# PWR_FG.net
KiCad netlist of a schematic drawn in Altium Designer
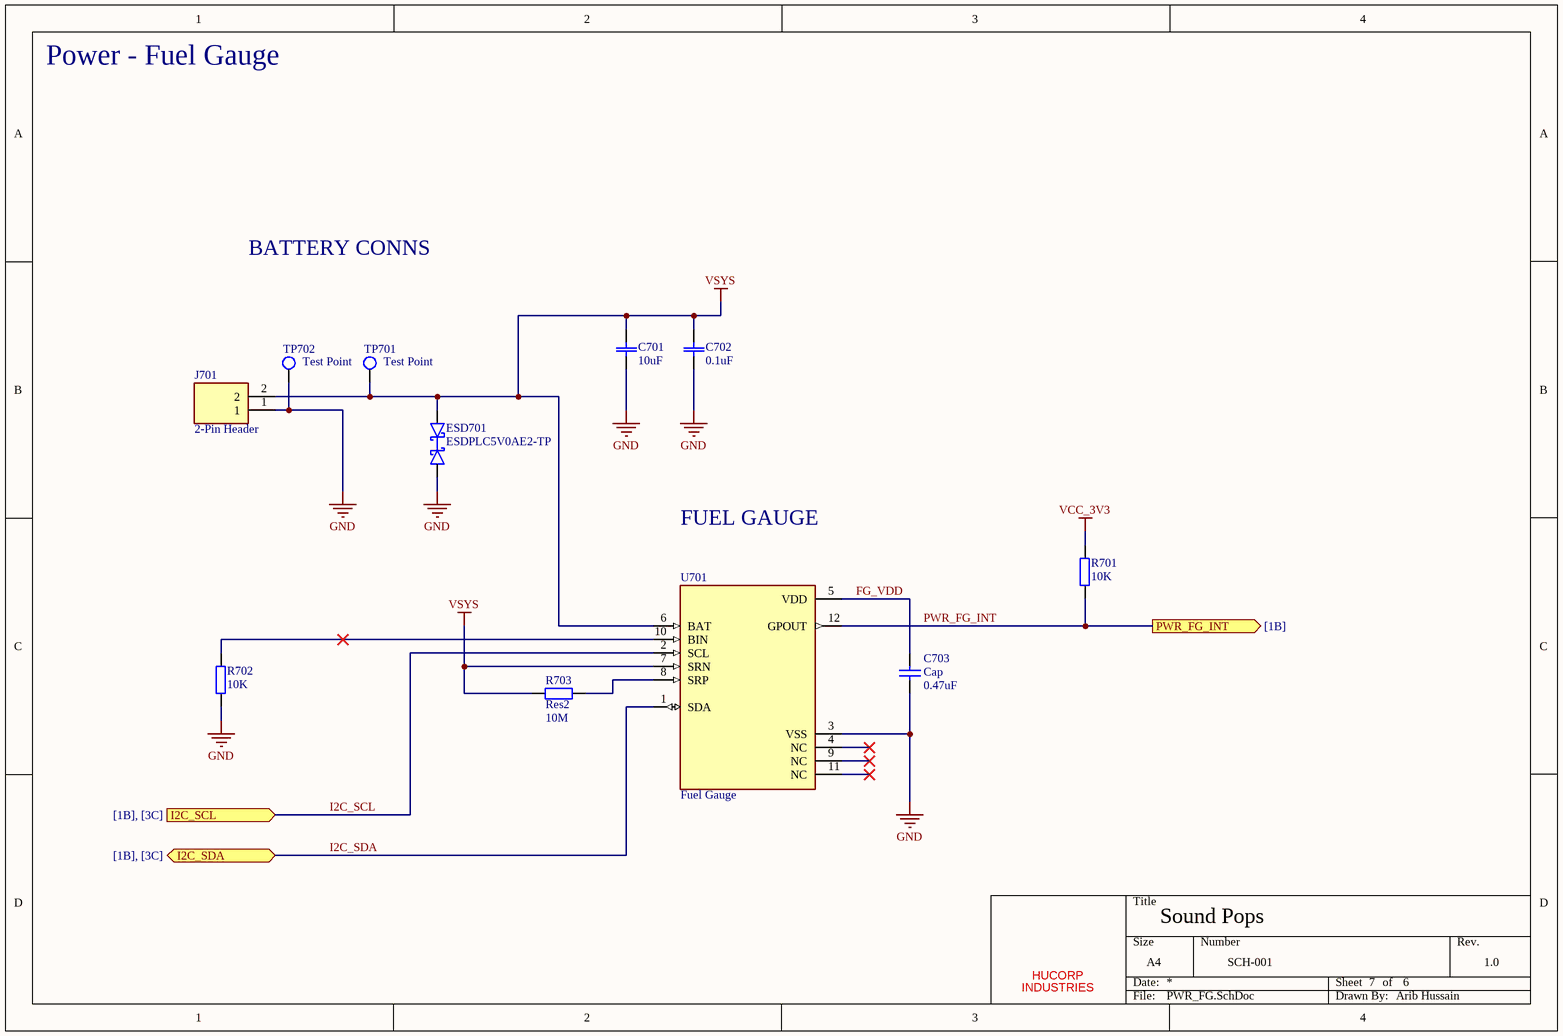
[diagram p0: PWR_FG.SchDoc]

(export (version "E")
  (design (tool "Eeschema 10.0.6"))
  (components
    (comp (ref "C701")
      (value "10uF")
      (footprint "CAP_CL10_SAM")
      (description "10 µF ±20% 6.3V Ceramic Capacitor X5R 0603 (1608 Metric)")
      (fields
        (field (name "MANUFACTURER_PART_NUMBER") "CL10A106MQ8NNNC")
        (field (name "Comment") "10 uF")
        (field (name "COPYRIGHT") "Copyright (C) 2022 Ultra Librarian. All rights reserved.")
      )
      (libsource (lib "Capacitors") (part "CL10A106MQ8NNNC"))
    )
    (comp (ref "C702")
      (value "0.1uF")
      (footprint "CAP_CL10_SAM")
      (description "CAP CER 0.1UF 25V X7R 0603")
      (fields
        (field (name "MANUFACTURER_PART_NUMBER") "CL10B104KA8NNNC")
        (field (name "Comment") "100 nF")
        (field (name "COPYRIGHT") "Copyright (C) 2022 Ultra Librarian. All rights reserved.")
      )
      (libsource (lib "Capacitors") (part "CL10B104KA8NNNC"))
    )
    (comp (ref "C703")
      (value "Cap")
      (footprint "RAD-0.3")
      (description "Capacitor")
      (fields (field (name "ALTIUM_VALUE") "0.47uF") (field (name "PUBLISHER") "Altium Limited"))
      (libsource (lib "Miscellaneous Devices") (part "Cap"))
    )
    (comp (ref "ESD701")
      (value "ESDPLC5V0AE2-TP")
      (footprint "ESDPLC5V0AE2")
      (description "TVS DIODE 5.5VWM 15VC 0201-A")
      (libsource (lib "PASSIVES") (part "ESDPLC5V0AE2-TP"))
    )
    (comp (ref "J701")
      (value "2-Pin Header")
      (footprint "TE_2-644861-2")
      (description "02P MTA100 SHRD HDR,W/O PEG SN")
      (fields (field (name "MP") "2-644861-2") (field (name "DIGI-KEY_PART_NUMBER") "A30931-ND"))
      (libsource (lib "MISC") (part "2-644861-2"))
    )
    (comp (ref "R701")
      (value "10K")
      (footprint "RES_RC0603_YAG")
      (description "RES 10K OHM 5% 1/10W 0603")
      (fields
        (field (name "MANUFACTURER_PART_NUMBER") "RC0603JR-1310KL")
        (field (name "COPYRIGHT") "Copyright (C) 2022 Ultra Librarian. All rights reserved.")
      )
      (libsource (lib "Resistors") (part "RC0603JR-1310KL"))
    )
    (comp (ref "R702")
      (value "10K")
      (footprint "RES_RC0603_YAG")
      (description "RES 10K OHM 5% 1/10W 0603")
      (fields
        (field (name "MANUFACTURER_PART_NUMBER") "RC0603JR-1310KL")
        (field (name "COPYRIGHT") "Copyright (C) 2022 Ultra Librarian. All rights reserved.")
      )
      (libsource (lib "Resistors") (part "RC0603JR-1310KL"))
    )
    (comp (ref "R703")
      (value "Res2")
      (footprint "AXIAL-0.4")
      (description "Resistor")
      (fields (field (name "ALTIUM_VALUE") "10M") (field (name "PUBLISHER") "Altium Limited"))
      (libsource (lib "Miscellaneous Devices") (part "Res2"))
    )
    (comp (ref "TP701")
      (value "Test Point")
      (footprint "TestPoint1")
      (description "General Test Point")
      (libsource (lib "Constants") (part "TestPoint1"))
    )
    (comp (ref "TP702")
      (value "Test Point")
      (footprint "TestPoint1")
      (description "General Test Point")
      (libsource (lib "Constants") (part "TestPoint1"))
    )
    (comp (ref "U701")
      (value "Fuel Gauge")
      (footprint "MISC:IC_BQ27441DRZR-G1A")
      (description "System-side Impedance Track battery fuel (gas) gauge 12-SON -40 to 85")
      (fields (field (name "MP") "BQ27441DRZR-G1A") (field (name "DIGI-KEY_PART_NUMBER") "296-39941-1-ND"))
      (libsource (lib "MISC") (part "BQ27441DRZR-G1A"))
    )
  )
  (nets
    (net (code "1") (name "/FG_VDD") (class "Default")
      (node (ref "C703") (pin "2") (pinfunction "2_2") (pintype "passive"))
      (node (ref "U701") (pin "5") (pinfunction "VDD_5") (pintype "power_in"))
    )
    (net (code "2") (name "/I2C_SCL") (class "Default")
      (node (ref "U701") (pin "2") (pinfunction "SCL_2") (pintype "input"))
    )
    (net (code "3") (name "/I2C_SDA") (class "Default")
      (node (ref "U701") (pin "1") (pinfunction "SDA_1") (pintype "bidirectional"))
    )
    (net (code "4") (name "/PWR_FG_INT") (class "Default")
      (node (ref "R701") (pin "1") (pinfunction "1_1") (pintype "passive"))
      (node (ref "U701") (pin "12") (pinfunction "GPOUT_12") (pintype "output"))
    )
    (net (code "5") (name "GND") (class "Default")
      (node (ref "C701") (pin "1") (pinfunction "1_1") (pintype "passive"))
      (node (ref "C702") (pin "1") (pinfunction "1_1") (pintype "passive"))
      (node (ref "C703") (pin "1") (pinfunction "1_1") (pintype "passive"))
      (node (ref "ESD701") (pin "2") (pinfunction "2_2") (pintype "passive"))
      (node (ref "J701") (pin "1") (pinfunction "1_1") (pintype "passive"))
      (node (ref "R702") (pin "1") (pinfunction "1_1") (pintype "passive"))
      (node (ref "TP702") (pin "1") (pinfunction "1_1") (pintype "passive"))
      (node (ref "U701") (pin "3") (pinfunction "VSS_3") (pintype "power_in"))
    )
    (net (code "6") (name "Net-(U701-BIN)") (class "Default")
      (node (ref "R702") (pin "2") (pinfunction "2_2") (pintype "passive"))
      (node (ref "U701") (pin "10") (pinfunction "BIN_10") (pintype "input"))
    )
    (net (code "7") (name "Net-(U701-SRP)") (class "Default")
      (node (ref "R703") (pin "1") (pinfunction "1_1") (pintype "passive"))
      (node (ref "U701") (pin "8") (pinfunction "SRP_8") (pintype "input"))
    )
    (net (code "8") (name "VCC_3V3") (class "Default")
      (node (ref "R701") (pin "2") (pinfunction "2_2") (pintype "passive"))
    )
    (net (code "9") (name "VSYS") (class "Default")
      (node (ref "C701") (pin "2") (pinfunction "2_2") (pintype "passive"))
      (node (ref "C702") (pin "2") (pinfunction "2_2") (pintype "passive"))
      (node (ref "ESD701") (pin "1") (pinfunction "27_1") (pintype "passive"))
      (node (ref "J701") (pin "2") (pinfunction "2_2") (pintype "passive"))
      (node (ref "R703") (pin "2") (pinfunction "2_2") (pintype "passive"))
      (node (ref "TP701") (pin "1") (pinfunction "1_1") (pintype "passive"))
      (node (ref "U701") (pin "6") (pinfunction "BAT_6") (pintype "input"))
      (node (ref "U701") (pin "7") (pinfunction "SRN_7") (pintype "input"))
    )
    (net (code "10") (name "unconnected-(U701-NC-Pad4)") (class "Default")
      (node (ref "U701") (pin "4") (pinfunction "NC_4") (pintype "power_in+no_connect"))
    )
    (net (code "11") (name "unconnected-(U701-NC-Pad9)") (class "Default")
      (node (ref "U701") (pin "9") (pinfunction "NC_9") (pintype "power_in+no_connect"))
    )
    (net (code "12") (name "unconnected-(U701-NC-Pad11)") (class "Default")
      (node (ref "U701") (pin "11") (pinfunction "NC_11") (pintype "power_in+no_connect"))
    )
  )
)
